# DB_PSU_1V2_2V5.net
KiCad netlist of a schematic drawn in Altium Designer
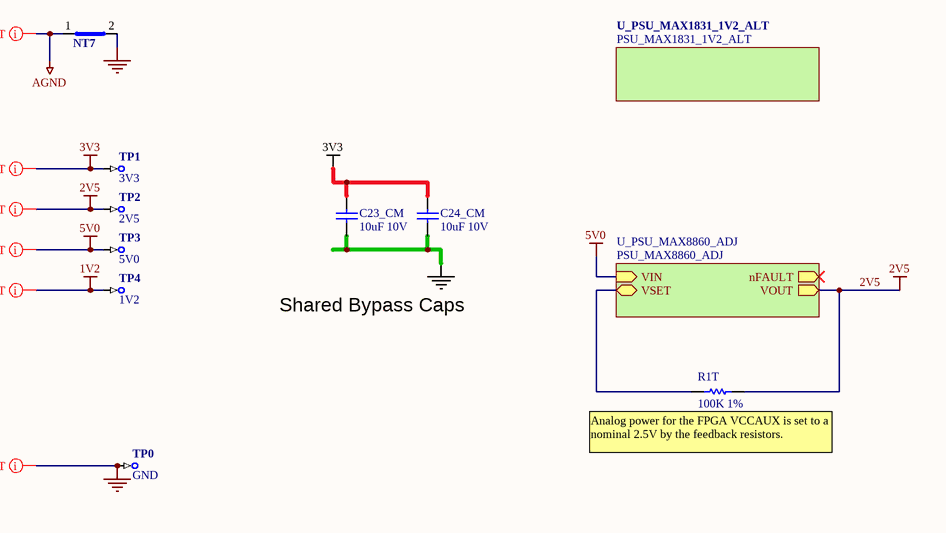
[diagram p0: DB_PSU_1V2_2V5.SCHDOC]

(export (version "E")
  (design (tool "Eeschema 10.0.6"))
  (components
    (comp (ref "C23_CM")
      (value "10uF 10V")
      (footprint "CAPC2012-STAR")
      (description "Capacitor, Ceramic, 10uF 10% 10V 0805 (2012) X5R")
      (fields (field (name "TOLERANCE") "10 %"))
      (libsource (lib "AltiumDesignLibrary") (part "CAP-NP"))
    )
    (comp (ref "C24_CM")
      (value "10uF 10V")
      (footprint "CAPC2012-STAR")
      (description "Capacitor, Ceramic, 10uF 10% 10V 0805 (2012) X5R")
      (fields (field (name "TOLERANCE") "10 %"))
      (libsource (lib "AltiumDesignLibrary") (part "CAP-NP"))
    )
    (comp (ref "NT7")
      (value "Net Tie SMT2")
      (footprint "NETTIE-SMT2-8X8")
      (description "Net-Tie, Surface Mount, 2 x 0.4mm x 0.2mm SMT Pads - For 0.2mm Track")
      (libsource (lib "AltiumDesignLibrary") (part "NETTIE-SMT2"))
    )
    (comp (ref "R1T")
      (value "100K 1%")
      (footprint "RESC1005-STAR")
      (description "Resistor, 100K 1% 0402 (1005)")
      (fields (field (name "TOLERANCE") "1 %"))
      (libsource (lib "AltiumDesignLibrary") (part "RES"))
    )
    (comp (ref "TP0")
      (value "GND")
      (footprint "TestPin")
      (description "Test Point, PCB Mount with Silkscreen Box")
      (libsource (lib "AltiumDesignLibrary") (part "TestPin"))
    )
    (comp (ref "TP1")
      (value "3V3")
      (footprint "TestPin")
      (description "Test Point, PCB Mount with Silkscreen Box")
      (libsource (lib "AltiumDesignLibrary") (part "TestPin"))
    )
    (comp (ref "TP2")
      (value "2V5")
      (footprint "TestPin")
      (description "Test Point, PCB Mount with Silkscreen Box")
      (libsource (lib "AltiumDesignLibrary") (part "TestPin"))
    )
    (comp (ref "TP3")
      (value "5V0")
      (footprint "TestPin")
      (description "Test Point, PCB Mount with Silkscreen Box")
      (libsource (lib "AltiumDesignLibrary") (part "TestPin"))
    )
    (comp (ref "TP4")
      (value "1V2")
      (footprint "TestPin")
      (description "Test Point, PCB Mount with Silkscreen Box")
      (libsource (lib "AltiumDesignLibrary") (part "TestPin"))
    )
  )
  (nets
    (net (code "1") (name "/VSET") (class "Default")
      (node (ref "R1T") (pin "1") (pinfunction "1_1") (pintype "passive"))
    )
    (net (code "3") (name "1V2") (class "Default")
      (node (ref "TP4") (pin "1") (pinfunction "1_1") (pintype "input"))
    )
    (net (code "4") (name "2V5") (class "Default")
      (node (ref "R1T") (pin "2") (pinfunction "2_2") (pintype "passive"))
      (node (ref "TP2") (pin "1") (pinfunction "1_1") (pintype "input"))
    )
    (net (code "5") (name "3V3") (class "Default")
      (node (ref "C23_CM") (pin "1") (pinfunction "1_1") (pintype "passive"))
      (node (ref "C24_CM") (pin "1") (pinfunction "1_1") (pintype "passive"))
      (node (ref "TP1") (pin "1") (pinfunction "1_1") (pintype "input"))
    )
    (net (code "6") (name "5V0") (class "Default")
      (node (ref "TP3") (pin "1") (pinfunction "1_1") (pintype "input"))
    )
    (net (code "7") (name "AGND") (class "Default")
      (node (ref "NT7") (pin "1") (pinfunction "Net1_1") (pintype "passive"))
    )
    (net (code "8") (name "GND") (class "Default")
      (node (ref "C23_CM") (pin "2") (pinfunction "2_2") (pintype "passive"))
      (node (ref "C24_CM") (pin "2") (pinfunction "2_2") (pintype "passive"))
      (node (ref "NT7") (pin "2") (pinfunction "Net2_2") (pintype "passive"))
      (node (ref "TP0") (pin "1") (pinfunction "1_1") (pintype "input"))
    )
  )
)
